# Wheel_Encoder_Adapter_Schmitt_74LVC.net
KiCad netlist of a schematic drawn in EAGLE
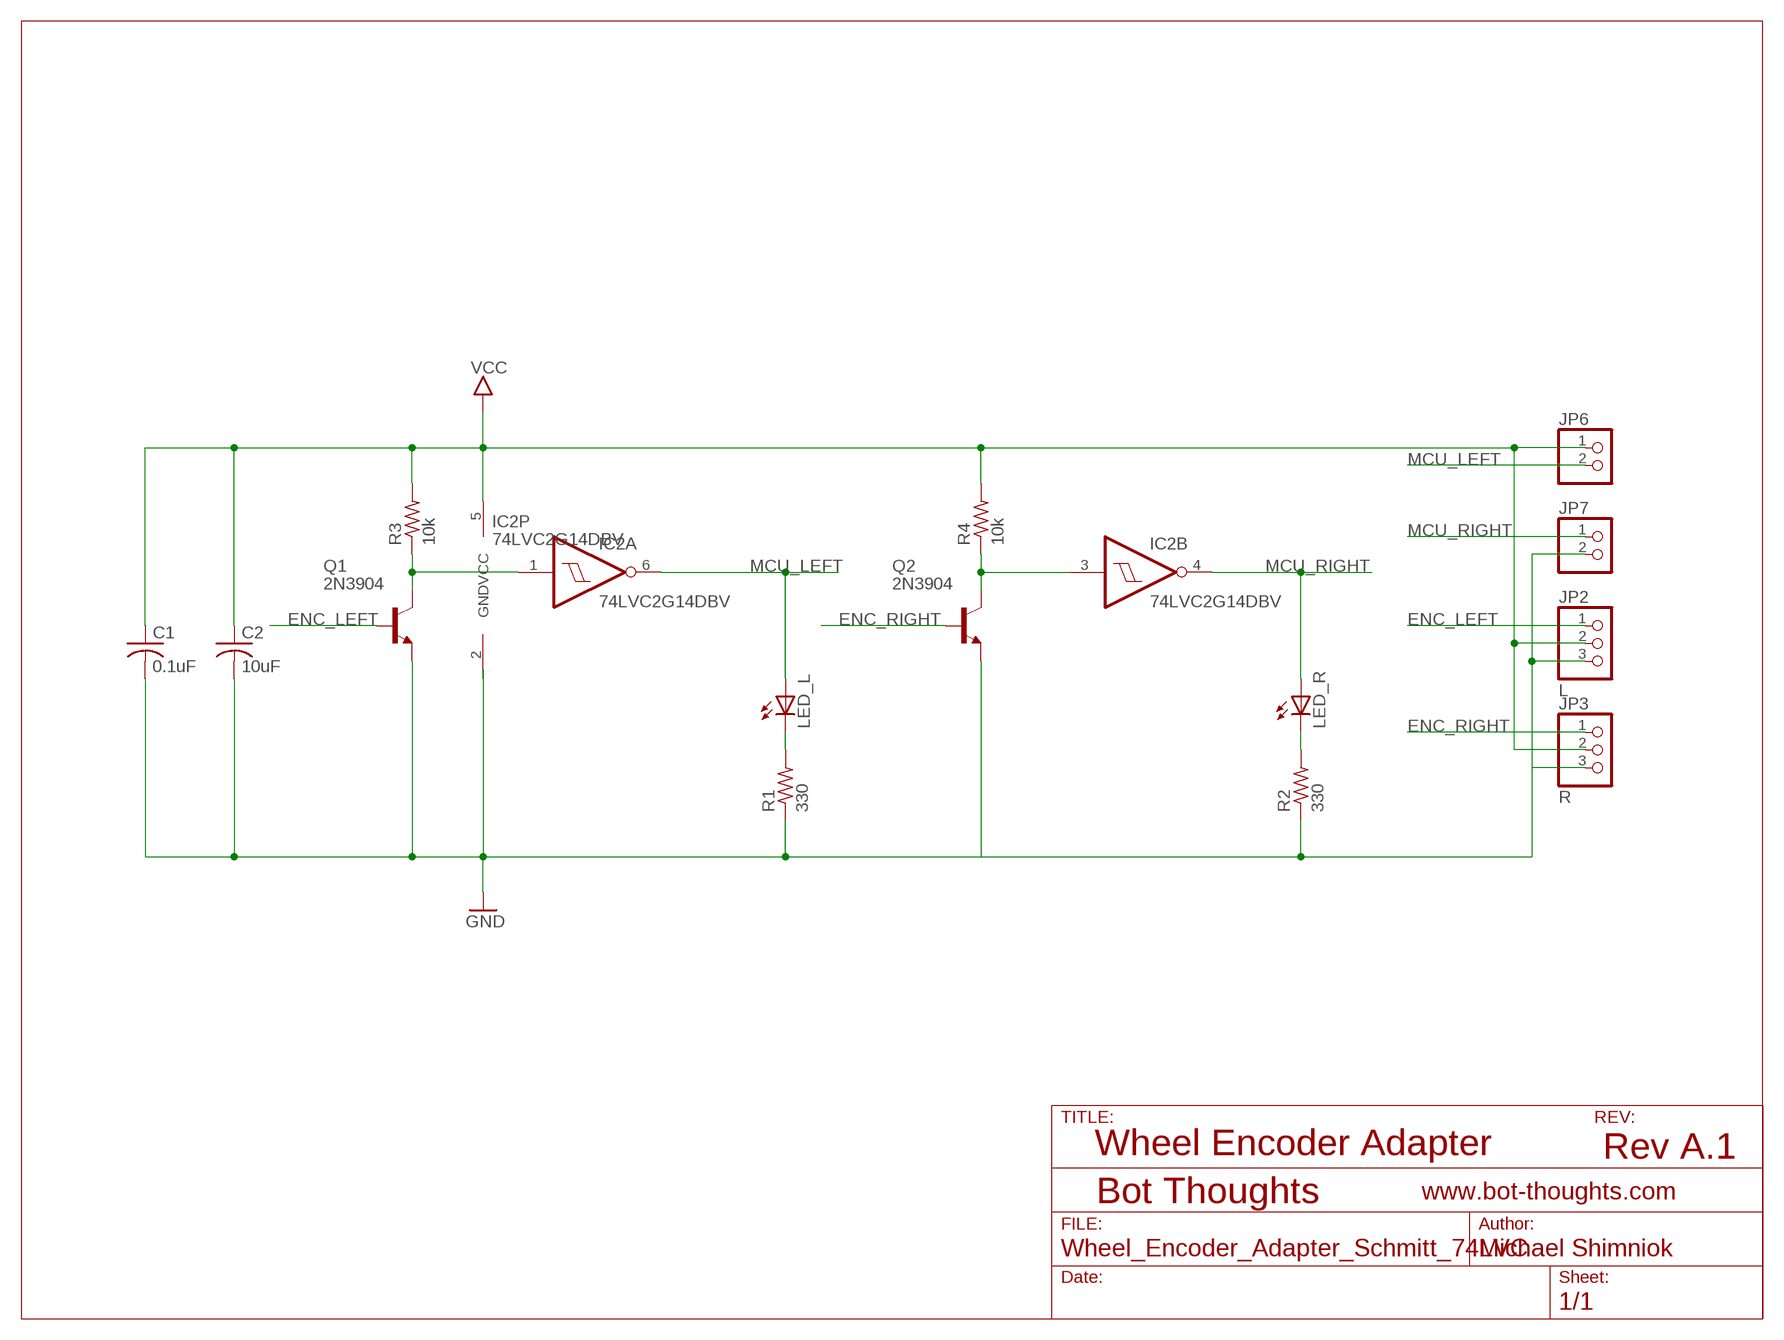
[diagram p0: schematic, sheet 1]

(export (version "E")
  (design (tool "Eeschema 10.0.6"))
  (components
    (comp (ref "C1")
      (value "0.1uF")
      (footprint "eagle-import:C0603")
      (libsource (lib "eagle-import") (part "C-USC0603"))
    )
    (comp (ref "C2")
      (value "10uF")
      (footprint "eagle-import:C0603")
      (libsource (lib "eagle-import") (part "C-USC0603"))
    )
    (comp (ref "IC2")
      (value "74LVC2G14DBV")
      (footprint "eagle-import:SOT23-6")
      (libsource (lib "eagle-import") (part "74LVC2G14DBV"))
    )
    (comp (ref "JP2")
      (value "L")
      (footprint "eagle-import:1X03-S")
      (libsource (lib "eagle-import") (part "PINHD-1X03_2.54-S"))
    )
    (comp (ref "JP3")
      (value "R")
      (footprint "eagle-import:1X03-S")
      (libsource (lib "eagle-import") (part "PINHD-1X03_2.54-S"))
    )
    (comp (ref "JP6")
      (value "PINHD-1X02_2.54-S")
      (footprint "eagle-import:1X02-S")
      (libsource (lib "eagle-import") (part "PINHD-1X02_2.54-S"))
    )
    (comp (ref "JP7")
      (value "PINHD-1X02_2.54-S")
      (footprint "eagle-import:1X02-S")
      (libsource (lib "eagle-import") (part "PINHD-1X02_2.54-S"))
    )
    (comp (ref "LED_L")
      (value "LEDCHIPLED_0805")
      (footprint "eagle-import:CHIPLED_0805")
      (libsource (lib "eagle-import") (part "LEDCHIPLED_0805"))
    )
    (comp (ref "LED_R")
      (value "LEDCHIPLED_0805")
      (footprint "eagle-import:CHIPLED_0805")
      (libsource (lib "eagle-import") (part "LEDCHIPLED_0805"))
    )
    (comp (ref "Q1")
      (value "2N3904")
      (footprint "eagle-import:SOT-23")
      (libsource (lib "eagle-import") (part "2N3904SMD"))
    )
    (comp (ref "Q2")
      (value "2N3904")
      (footprint "eagle-import:SOT-23")
      (libsource (lib "eagle-import") (part "2N3904SMD"))
    )
    (comp (ref "R1")
      (value "330")
      (footprint "eagle-import:R0603")
      (libsource (lib "eagle-import") (part "R-US_R0603"))
    )
    (comp (ref "R2")
      (value "330")
      (footprint "eagle-import:R0603")
      (libsource (lib "eagle-import") (part "R-US_R0603"))
    )
    (comp (ref "R3")
      (value "10k")
      (footprint "eagle-import:R0603")
      (libsource (lib "eagle-import") (part "R-US_R0603"))
    )
    (comp (ref "R4")
      (value "10k")
      (footprint "eagle-import:R0603")
      (libsource (lib "eagle-import") (part "R-US_R0603"))
    )
  )
  (nets
    (net (code "1") (name "/ENC_LEFT") (class "Default")
      (node (ref "JP2") (pin "1") (pinfunction "1_1") (pintype "passive"))
      (node (ref "Q1") (pin "3") (pinfunction "B_3") (pintype "passive"))
    )
    (net (code "2") (name "/ENC_RIGHT") (class "Default")
      (node (ref "JP3") (pin "1") (pinfunction "1_1") (pintype "passive"))
      (node (ref "Q2") (pin "3") (pinfunction "B_3") (pintype "passive"))
    )
    (net (code "3") (name "/MCU_LEFT") (class "Default")
      (node (ref "IC2") (pin "6") (pinfunction "O_6") (pintype "output"))
      (node (ref "JP6") (pin "2") (pinfunction "2_2") (pintype "passive"))
      (node (ref "LED_L") (pin "A") (pinfunction "A_A") (pintype "passive"))
    )
    (net (code "4") (name "/MCU_RIGHT") (class "Default")
      (node (ref "IC2") (pin "4") (pinfunction "O_4") (pintype "output"))
      (node (ref "JP7") (pin "1") (pinfunction "1_1") (pintype "passive"))
      (node (ref "LED_R") (pin "A") (pinfunction "A_A") (pintype "passive"))
    )
    (net (code "5") (name "GND") (class "Default")
      (node (ref "C1") (pin "2") (pinfunction "2_2") (pintype "passive"))
      (node (ref "C2") (pin "2") (pinfunction "2_2") (pintype "passive"))
      (node (ref "IC2") (pin "2") (pinfunction "GND_2") (pintype "power_in"))
      (node (ref "JP2") (pin "3") (pinfunction "3_3") (pintype "passive"))
      (node (ref "JP3") (pin "3") (pinfunction "3_3") (pintype "passive"))
      (node (ref "JP7") (pin "2") (pinfunction "2_2") (pintype "passive"))
      (node (ref "Q1") (pin "2") (pinfunction "E_2") (pintype "passive"))
      (node (ref "Q2") (pin "2") (pinfunction "E_2") (pintype "passive"))
      (node (ref "R1") (pin "1") (pinfunction "1_1") (pintype "passive"))
      (node (ref "R2") (pin "1") (pinfunction "1_1") (pintype "passive"))
    )
    (net (code "6") (name "Net-(IC2A-I)") (class "Default")
      (node (ref "IC2") (pin "1") (pinfunction "I_1") (pintype "input"))
      (node (ref "Q1") (pin "1") (pinfunction "C_1") (pintype "passive"))
      (node (ref "R3") (pin "1") (pinfunction "1_1") (pintype "passive"))
    )
    (net (code "7") (name "Net-(IC2B-I)") (class "Default")
      (node (ref "IC2") (pin "3") (pinfunction "I_3") (pintype "input"))
      (node (ref "Q2") (pin "1") (pinfunction "C_1") (pintype "passive"))
      (node (ref "R4") (pin "1") (pinfunction "1_1") (pintype "passive"))
    )
    (net (code "8") (name "Net-(LED_L-PadC)") (class "Default")
      (node (ref "LED_L") (pin "C") (pinfunction "C_C") (pintype "passive"))
      (node (ref "R1") (pin "2") (pinfunction "2_2") (pintype "passive"))
    )
    (net (code "9") (name "Net-(LED_R-PadC)") (class "Default")
      (node (ref "LED_R") (pin "C") (pinfunction "C_C") (pintype "passive"))
      (node (ref "R2") (pin "2") (pinfunction "2_2") (pintype "passive"))
    )
    (net (code "10") (name "VCC") (class "Default")
      (node (ref "C1") (pin "1") (pinfunction "1_1") (pintype "passive"))
      (node (ref "C2") (pin "1") (pinfunction "1_1") (pintype "passive"))
      (node (ref "IC2") (pin "5") (pinfunction "VCC_5") (pintype "power_in"))
      (node (ref "JP2") (pin "2") (pinfunction "2_2") (pintype "passive"))
      (node (ref "JP3") (pin "2") (pinfunction "2_2") (pintype "passive"))
      (node (ref "JP6") (pin "1") (pinfunction "1_1") (pintype "passive"))
      (node (ref "R3") (pin "2") (pinfunction "2_2") (pintype "passive"))
      (node (ref "R4") (pin "2") (pinfunction "2_2") (pintype "passive"))
    )
  )
)
